# Payload.net
KiCad netlist of a schematic drawn in EAGLE
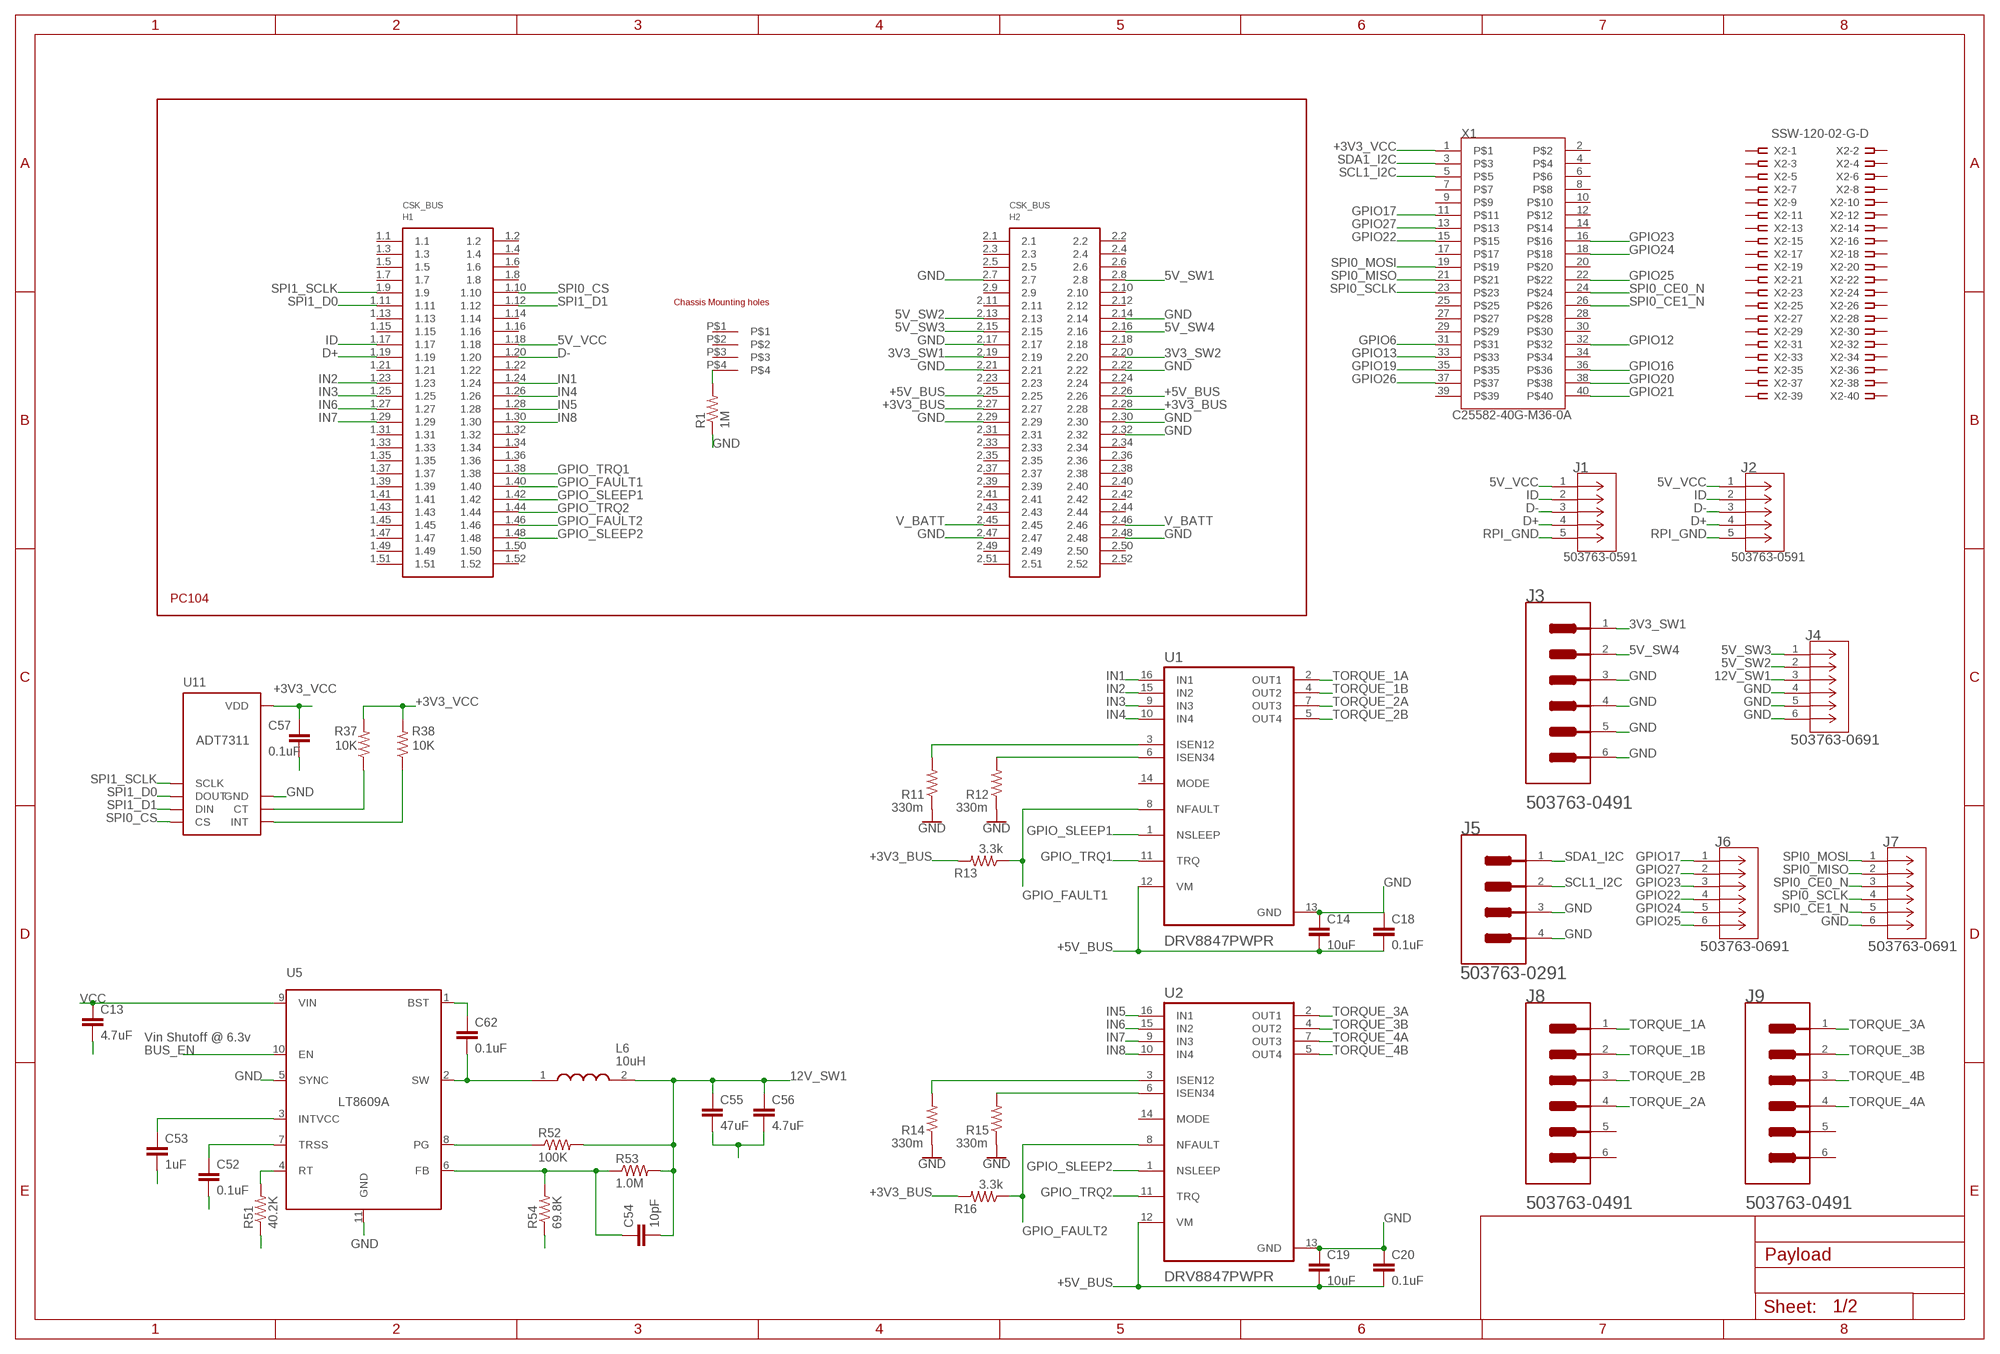
[diagram p0: schematic, sheet 1]
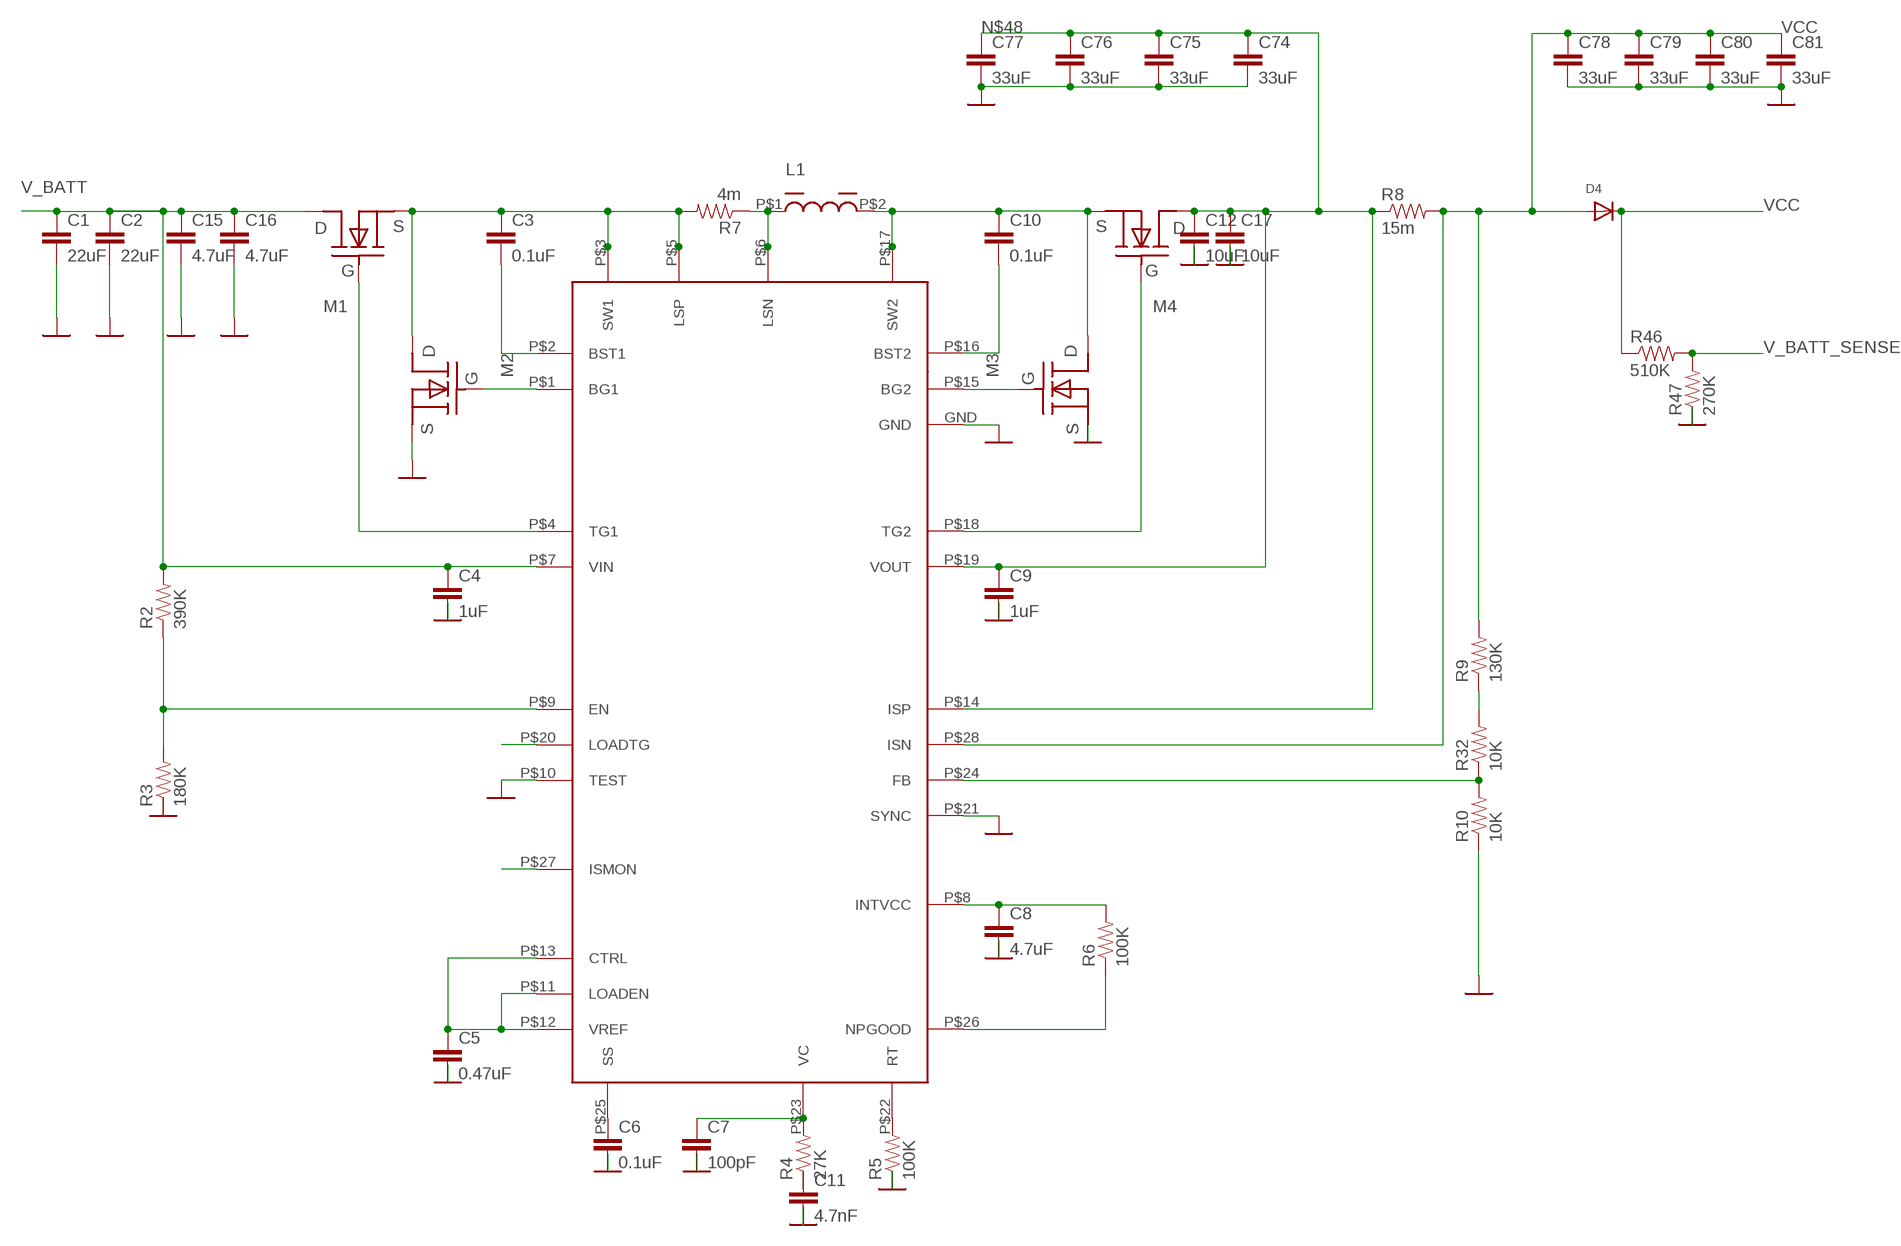
[diagram p1: schematic, sheet 2]

(export (version "E")
  (design (tool "Eeschema 10.0.6"))
  (components
    (comp (ref "C13")
      (value "4.7uF")
      (footprint "eagle-import:0805")
      (libsource (lib "eagle-import") (part "CAP0805"))
    )
    (comp (ref "C14")
      (value "10uF")
      (footprint "eagle-import:0805")
      (libsource (lib "eagle-import") (part "CAP0805"))
    )
    (comp (ref "C18")
      (value "0.1uF")
      (footprint "eagle-import:0805")
      (libsource (lib "eagle-import") (part "CAP0805"))
    )
    (comp (ref "C19")
      (value "10uF")
      (footprint "eagle-import:0805")
      (libsource (lib "eagle-import") (part "CAP0805"))
    )
    (comp (ref "C20")
      (value "0.1uF")
      (footprint "eagle-import:0805")
      (libsource (lib "eagle-import") (part "CAP0805"))
    )
    (comp (ref "C52")
      (value "0.1uF")
      (footprint "eagle-import:0805")
      (libsource (lib "eagle-import") (part "CAP0805"))
    )
    (comp (ref "C53")
      (value "1uF")
      (footprint "eagle-import:0805")
      (libsource (lib "eagle-import") (part "CAP0805"))
    )
    (comp (ref "C54")
      (value "10pF")
      (footprint "eagle-import:0805")
      (libsource (lib "eagle-import") (part "CAP0805"))
    )
    (comp (ref "C55")
      (value "47uF")
      (footprint "eagle-import:1210")
      (libsource (lib "eagle-import") (part "CAP1210"))
    )
    (comp (ref "C56")
      (value "4.7uF")
      (footprint "eagle-import:0805")
      (libsource (lib "eagle-import") (part "CAP0805"))
    )
    (comp (ref "C57")
      (value "0.1uF")
      (footprint "eagle-import:0805")
      (libsource (lib "eagle-import") (part "CAP0805"))
    )
    (comp (ref "C62")
      (value "0.1uF")
      (footprint "eagle-import:0805")
      (libsource (lib "eagle-import") (part "CAP0805"))
    )
    (comp (ref "H1")
      (value "PC104_WCONN")
      (footprint "eagle-import:PC104_WCONN")
      (libsource (lib "eagle-import") (part "PC104_WCONN"))
    )
    (comp (ref "J1")
      (value "503763-0591")
      (footprint "eagle-import:CONN_5037630591_MOL")
      (fields (field (name "COPYRIGHT") "Copyright (C) 2018 Accelerated Designs. All rights reserved"))
      (libsource (lib "eagle-import") (part "503763-0591"))
    )
    (comp (ref "J2")
      (value "503763-0591")
      (footprint "eagle-import:CONN_5037630591_MOL")
      (fields (field (name "COPYRIGHT") "Copyright (C) 2018 Accelerated Designs. All rights reserved"))
      (libsource (lib "eagle-import") (part "503763-0591"))
    )
    (comp (ref "J3")
      (value "MOLEX_503763-0491MOLEX_503763-0491_0_0")
      (footprint "eagle-import:MOLEX_503763-0491_0")
      (fields
        (field (name "DIGIKEY_PART_NUMBER") "WM10655CT-ND")
        (field (name "MF") "Molex")
        (field (name "MOUSER_PART_NUMBER") "538-503763-0491")
      )
      (libsource (lib "eagle-import") (part "MOLEX_503763-0491MOLEX_503763-0491_0_0"))
    )
    (comp (ref "J4")
      (value "503763-0691")
      (footprint "eagle-import:CONN_503763-0691_MOL")
      (fields (field (name "COPYRIGHT") "Copyright (C) 2018 Accelerated Designs. All rights reserved"))
      (libsource (lib "eagle-import") (part "503763-0691"))
    )
    (comp (ref "J5")
      (value "MOLEX_503763-0291MOLEX_503763-0291_0_0")
      (footprint "eagle-import:MOLEX_503763-0291_0")
      (fields
        (field (name "DIGIKEY_PART_NUMBER") "WM10654CT-ND")
        (field (name "MF") "Molex")
        (field (name "MOUSER_PART_NUMBER") "538-503763-0291")
      )
      (libsource (lib "eagle-import") (part "MOLEX_503763-0291MOLEX_503763-0291_0_0"))
    )
    (comp (ref "J6")
      (value "503763-0691")
      (footprint "eagle-import:CONN_503763-0691_MOL")
      (fields (field (name "COPYRIGHT") "Copyright (C) 2018 Accelerated Designs. All rights reserved"))
      (libsource (lib "eagle-import") (part "503763-0691"))
    )
    (comp (ref "J7")
      (value "503763-0691")
      (footprint "eagle-import:CONN_503763-0691_MOL")
      (fields (field (name "COPYRIGHT") "Copyright (C) 2018 Accelerated Designs. All rights reserved"))
      (libsource (lib "eagle-import") (part "503763-0691"))
    )
    (comp (ref "J8")
      (value "MOLEX_503763-0491MOLEX_503763-0491_0_0")
      (footprint "eagle-import:MOLEX_503763-0491_0")
      (fields
        (field (name "DIGIKEY_PART_NUMBER") "WM10655CT-ND")
        (field (name "MF") "Molex")
        (field (name "MOUSER_PART_NUMBER") "538-503763-0491")
      )
      (libsource (lib "eagle-import") (part "MOLEX_503763-0491MOLEX_503763-0491_0_0"))
    )
    (comp (ref "J9")
      (value "MOLEX_503763-0491MOLEX_503763-0491_0_0")
      (footprint "eagle-import:MOLEX_503763-0491_0")
      (fields
        (field (name "DIGIKEY_PART_NUMBER") "WM10655CT-ND")
        (field (name "MF") "Molex")
        (field (name "MOUSER_PART_NUMBER") "538-503763-0491")
      )
      (libsource (lib "eagle-import") (part "MOLEX_503763-0491MOLEX_503763-0491_0_0"))
    )
    (comp (ref "L6")
      (value "10uH")
      (footprint "eagle-import:XFL4030472MEB")
      (fields
        (field (name "ARROW_PART_NUMBER") "XFL4020-222MEC")
        (field (name "MOUSER_PART_NUMBER") "994-XFL4020-222MEC")
      )
      (libsource (lib "eagle-import") (part "XFL4020-222MEC"))
    )
    (comp (ref "R1")
      (value "1M")
      (footprint "eagle-import:0805")
      (libsource (lib "eagle-import") (part "RESISTOR0805-RES"))
    )
    (comp (ref "R11")
      (value "330m")
      (footprint "eagle-import:0805")
      (libsource (lib "eagle-import") (part "RESISTOR0805-RES"))
    )
    (comp (ref "R12")
      (value "330m")
      (footprint "eagle-import:0805")
      (libsource (lib "eagle-import") (part "RESISTOR0805-RES"))
    )
    (comp (ref "R13")
      (value "3.3k")
      (footprint "eagle-import:0805")
      (libsource (lib "eagle-import") (part "RESISTOR0805-RES"))
    )
    (comp (ref "R14")
      (value "330m")
      (footprint "eagle-import:0805")
      (libsource (lib "eagle-import") (part "RESISTOR0805-RES"))
    )
    (comp (ref "R15")
      (value "330m")
      (footprint "eagle-import:0805")
      (libsource (lib "eagle-import") (part "RESISTOR0805-RES"))
    )
    (comp (ref "R16")
      (value "3.3k")
      (footprint "eagle-import:0805")
      (libsource (lib "eagle-import") (part "RESISTOR0805-RES"))
    )
    (comp (ref "R37")
      (value "10K")
      (footprint "eagle-import:0805")
      (libsource (lib "eagle-import") (part "RESISTOR0805-RES"))
    )
    (comp (ref "R38")
      (value "10K")
      (footprint "eagle-import:0805")
      (libsource (lib "eagle-import") (part "RESISTOR0805-RES"))
    )
    (comp (ref "R51")
      (value "40.2K")
      (footprint "eagle-import:0805")
      (libsource (lib "eagle-import") (part "RESISTOR0805-RES"))
    )
    (comp (ref "R52")
      (value "100K")
      (footprint "eagle-import:0805")
      (libsource (lib "eagle-import") (part "RESISTOR0805-RES"))
    )
    (comp (ref "R53")
      (value "1.0M")
      (footprint "eagle-import:0805")
      (libsource (lib "eagle-import") (part "RESISTOR0805-RES"))
    )
    (comp (ref "R54")
      (value "69.8K")
      (footprint "eagle-import:0805")
      (libsource (lib "eagle-import") (part "RESISTOR0805-RES"))
    )
    (comp (ref "U1")
      (value "DRV8847PWPR")
      (footprint "eagle-import:SOP65P640X120-17N")
      (fields (field (name "MF") "Texas Instruments"))
      (libsource (lib "eagle-import") (part "DRV8847PWPR"))
    )
    (comp (ref "U2")
      (value "DRV8847PWPR")
      (footprint "eagle-import:SOP65P640X120-17N")
      (fields (field (name "MF") "Texas Instruments"))
      (libsource (lib "eagle-import") (part "DRV8847PWPR"))
    )
    (comp (ref "U5")
      (value "LT8609A")
      (footprint "eagle-import:MSOP-10_MSE")
      (libsource (lib "eagle-import") (part "LT8609A"))
    )
    (comp (ref "U11")
      (value "ADT7311")
      (footprint "eagle-import:SOIC-8")
      (libsource (lib "eagle-import") (part "ADT7311"))
    )
    (comp (ref "X1")
      (value "C25582-40G-M36-0A")
      (footprint "eagle-import:ADAFRUIT_C25582-40G-M36-0A_0")
      (libsource (lib "eagle-import") (part "C25582-40G-M36-0A"))
    )
    (comp (ref "X2")
      (value "SSW-120-02-G-D")
      (footprint "eagle-import:SSW-120-02-G-D")
      (fields (field (name "MF") "Samtec Inc."))
      (libsource (lib "eagle-import") (part "SSW-120-02-G-D"))
    )
    (comp (ref "C1")
      (value "22uF")
      (footprint "eagle-import:0805")
      (libsource (lib "eagle-import") (part "CAP0805"))
    )
    (comp (ref "C2")
      (value "22uF")
      (footprint "eagle-import:0805")
      (libsource (lib "eagle-import") (part "CAP0805"))
    )
    (comp (ref "C3")
      (value "0.1uF")
      (footprint "eagle-import:0805")
      (libsource (lib "eagle-import") (part "CAP0805"))
    )
    (comp (ref "C4")
      (value "1uF")
      (footprint "eagle-import:0805")
      (libsource (lib "eagle-import") (part "CAP0805"))
    )
    (comp (ref "C5")
      (value "0.47uF")
      (footprint "eagle-import:0805")
      (libsource (lib "eagle-import") (part "CAP0805"))
    )
    (comp (ref "C6")
      (value "0.1uF")
      (footprint "eagle-import:0805")
      (libsource (lib "eagle-import") (part "CAP0805"))
    )
    (comp (ref "C7")
      (value "100pF")
      (footprint "eagle-import:0805")
      (libsource (lib "eagle-import") (part "CAP0805"))
    )
    (comp (ref "C8")
      (value "4.7uF")
      (footprint "eagle-import:0805")
      (libsource (lib "eagle-import") (part "CAP0805"))
    )
    (comp (ref "C9")
      (value "1uF")
      (footprint "eagle-import:0805")
      (libsource (lib "eagle-import") (part "CAP0805"))
    )
    (comp (ref "C10")
      (value "0.1uF")
      (footprint "eagle-import:0805")
      (libsource (lib "eagle-import") (part "CAP0805"))
    )
    (comp (ref "C11")
      (value "4.7nF")
      (footprint "eagle-import:0805")
      (libsource (lib "eagle-import") (part "CAP0805"))
    )
    (comp (ref "C12")
      (value "10uF")
      (footprint "eagle-import:0805")
      (libsource (lib "eagle-import") (part "CAP0805"))
    )
    (comp (ref "C15")
      (value "4.7uF")
      (footprint "eagle-import:0805")
      (libsource (lib "eagle-import") (part "CAP0805"))
    )
    (comp (ref "C16")
      (value "4.7uF")
      (footprint "eagle-import:0805")
      (libsource (lib "eagle-import") (part "CAP0805"))
    )
    (comp (ref "C17")
      (value "10uF")
      (footprint "eagle-import:0805")
      (libsource (lib "eagle-import") (part "CAP0805"))
    )
    (comp (ref "C74")
      (value "33uF")
      (footprint "eagle-import:1206")
      (libsource (lib "eagle-import") (part "CAP1206"))
    )
    (comp (ref "C75")
      (value "33uF")
      (footprint "eagle-import:1206")
      (libsource (lib "eagle-import") (part "CAP1206"))
    )
    (comp (ref "C76")
      (value "33uF")
      (footprint "eagle-import:1206")
      (libsource (lib "eagle-import") (part "CAP1206"))
    )
    (comp (ref "C77")
      (value "33uF")
      (footprint "eagle-import:1206")
      (libsource (lib "eagle-import") (part "CAP1206"))
    )
    (comp (ref "C78")
      (value "33uF")
      (footprint "eagle-import:1206")
      (libsource (lib "eagle-import") (part "CAP1206"))
    )
    (comp (ref "C79")
      (value "33uF")
      (footprint "eagle-import:1206")
      (libsource (lib "eagle-import") (part "CAP1206"))
    )
    (comp (ref "C80")
      (value "33uF")
      (footprint "eagle-import:1206")
      (libsource (lib "eagle-import") (part "CAP1206"))
    )
    (comp (ref "C81")
      (value "33uF")
      (footprint "eagle-import:1206")
      (libsource (lib "eagle-import") (part "CAP1206"))
    )
    (comp (ref "D4")
      (value "DIODE_SOD-123FL")
      (footprint "eagle-import:SOD-123FL")
      (libsource (lib "eagle-import") (part "DIODE_SOD-123FL"))
    )
    (comp (ref "L1")
      (value "6uH")
      (footprint "eagle-import:7443551600")
      (libsource (lib "eagle-import") (part "7443551600"))
    )
    (comp (ref "M1")
      (value "BSZ100N06LS3")
      (footprint "eagle-import:BSZ100N06LS3")
      (libsource (lib "eagle-import") (part "BSZ100N06LS3"))
    )
    (comp (ref "M2")
      (value "BSZ100N06LS3")
      (footprint "eagle-import:BSZ100N06LS3")
      (libsource (lib "eagle-import") (part "BSZ100N06LS3"))
    )
    (comp (ref "M3")
      (value "BSZ033NE2LS5")
      (footprint "eagle-import:BSZ100N06LS3")
      (libsource (lib "eagle-import") (part "BSZ100N06LS3"))
    )
    (comp (ref "M4")
      (value "BSZ033NE2LS5")
      (footprint "eagle-import:BSZ100N06LS3")
      (libsource (lib "eagle-import") (part "BSZ100N06LS3"))
    )
    (comp (ref "R2")
      (value "390K")
      (footprint "eagle-import:0805")
      (libsource (lib "eagle-import") (part "RESISTOR0805-RES"))
    )
    (comp (ref "R3")
      (value "180K")
      (footprint "eagle-import:0805")
      (libsource (lib "eagle-import") (part "RESISTOR0805-RES"))
    )
    (comp (ref "R4")
      (value "27K")
      (footprint "eagle-import:0805")
      (libsource (lib "eagle-import") (part "RESISTOR0805-RES"))
    )
    (comp (ref "R5")
      (value "100K")
      (footprint "eagle-import:0805")
      (libsource (lib "eagle-import") (part "RESISTOR0805-RES"))
    )
    (comp (ref "R6")
      (value "100K")
      (footprint "eagle-import:0805")
      (libsource (lib "eagle-import") (part "RESISTOR0805-RES"))
    )
    (comp (ref "R7")
      (value "4m")
      (footprint "eagle-import:0805")
      (libsource (lib "eagle-import") (part "RESISTOR0805-RES"))
    )
    (comp (ref "R8")
      (value "15m")
      (footprint "eagle-import:0805")
      (libsource (lib "eagle-import") (part "RESISTOR0805-RES"))
    )
    (comp (ref "R9")
      (value "130K")
      (footprint "eagle-import:0805")
      (libsource (lib "eagle-import") (part "RESISTOR0805-RES"))
    )
    (comp (ref "R10")
      (value "10K")
      (footprint "eagle-import:0805")
      (libsource (lib "eagle-import") (part "RESISTOR0805-RES"))
    )
    (comp (ref "R32")
      (value "10K")
      (footprint "eagle-import:0805")
      (libsource (lib "eagle-import") (part "RESISTOR0805-RES"))
    )
    (comp (ref "R46")
      (value "510K")
      (footprint "eagle-import:0805")
      (libsource (lib "eagle-import") (part "RESISTOR0805-RES"))
    )
    (comp (ref "R47")
      (value "270K")
      (footprint "eagle-import:0805")
      (libsource (lib "eagle-import") (part "RESISTOR0805-RES"))
    )
    (comp (ref "U$2")
      (value "LT8309EFE")
      (footprint "eagle-import:LT8309EFE")
      (libsource (lib "eagle-import") (part "LT8309EFE"))
    )
  )
  (nets
    (net (code "1") (name "+3V3_BUS") (class "Default")
      (node (ref "H1") (pin "2.27") (pinfunction "2.27_2.27") (pintype "bidirectional"))
      (node (ref "H1") (pin "2.28") (pinfunction "2.28_2.28") (pintype "bidirectional"))
      (node (ref "R13") (pin "2") (pinfunction "2_2") (pintype "passive"))
      (node (ref "R16") (pin "2") (pinfunction "2_2") (pintype "passive"))
    )
    (net (code "2") (name "+3V3_VCC") (class "Default")
      (node (ref "C57") (pin "1") (pinfunction "1_1") (pintype "passive"))
      (node (ref "R37") (pin "2") (pinfunction "2_2") (pintype "passive"))
      (node (ref "R38") (pin "2") (pinfunction "2_2") (pintype "passive"))
      (node (ref "U11") (pin "8") (pinfunction "VDD_8") (pintype "bidirectional"))
      (node (ref "X1") (pin "1") (pinfunction "P$1_1") (pintype "bidirectional"))
    )
    (net (code "3") (name "+5V_BUS") (class "Default")
      (node (ref "C14") (pin "2") (pinfunction "2_2") (pintype "passive"))
      (node (ref "C18") (pin "2") (pinfunction "2_2") (pintype "passive"))
      (node (ref "C19") (pin "2") (pinfunction "2_2") (pintype "passive"))
      (node (ref "C20") (pin "2") (pinfunction "2_2") (pintype "passive"))
      (node (ref "H1") (pin "2.25") (pinfunction "2.25_2.25") (pintype "bidirectional"))
      (node (ref "H1") (pin "2.26") (pinfunction "2.26_2.26") (pintype "bidirectional"))
      (node (ref "U1") (pin "12") (pinfunction "VM_12") (pintype "bidirectional"))
      (node (ref "U2") (pin "12") (pinfunction "VM_12") (pintype "bidirectional"))
    )
    (net (code "4") (name "3V3_SW1") (class "Default")
      (node (ref "H1") (pin "2.19") (pinfunction "2.19_2.19") (pintype "bidirectional"))
      (node (ref "J3") (pin "1") (pinfunction "1_1") (pintype "passive"))
    )
    (net (code "5") (name "3V3_SW2") (class "Default")
      (node (ref "H1") (pin "2.20") (pinfunction "2.20_2.20") (pintype "bidirectional"))
    )
    (net (code "6") (name "5V_SW1") (class "Default")
      (node (ref "H1") (pin "2.8") (pinfunction "2.8_2.8") (pintype "bidirectional"))
    )
    (net (code "7") (name "5V_SW2") (class "Default")
      (node (ref "H1") (pin "2.13") (pinfunction "2.13_2.13") (pintype "bidirectional"))
      (node (ref "J4") (pin "2") (pinfunction "2_2") (pintype "passive"))
    )
    (net (code "8") (name "5V_SW3") (class "Default")
      (node (ref "H1") (pin "2.15") (pinfunction "2.15_2.15") (pintype "bidirectional"))
      (node (ref "J4") (pin "1") (pinfunction "1_1") (pintype "passive"))
    )
    (net (code "9") (name "5V_SW4") (class "Default")
      (node (ref "H1") (pin "2.16") (pinfunction "2.16_2.16") (pintype "bidirectional"))
      (node (ref "J3") (pin "2") (pinfunction "2_2") (pintype "passive"))
    )
    (net (code "10") (name "5V_VCC") (class "Default")
      (node (ref "H1") (pin "1.18") (pinfunction "1.18_1.18") (pintype "bidirectional"))
      (node (ref "J1") (pin "1") (pinfunction "1_1") (pintype "passive"))
      (node (ref "J2") (pin "1") (pinfunction "1_1") (pintype "passive"))
    )
    (net (code "11") (name "12V_SW1") (class "Default")
      (node (ref "C54") (pin "2") (pinfunction "2_2") (pintype "passive"))
      (node (ref "C55") (pin "1") (pinfunction "1_1") (pintype "passive"))
      (node (ref "C56") (pin "1") (pinfunction "1_1") (pintype "passive"))
      (node (ref "J4") (pin "3") (pinfunction "3_3") (pintype "passive"))
      (node (ref "L6") (pin "2") (pinfunction "2_2") (pintype "bidirectional"))
      (node (ref "R52") (pin "2") (pinfunction "2_2") (pintype "passive"))
      (node (ref "R53") (pin "2") (pinfunction "2_2") (pintype "passive"))
    )
    (net (code "12") (name "BUS_EN") (class "Default")
      (node (ref "U5") (pin "10") (pinfunction "EN_10") (pintype "bidirectional"))
    )
    (net (code "13") (name "D+") (class "Default")
      (node (ref "H1") (pin "1.19") (pinfunction "1.19_1.19") (pintype "bidirectional"))
      (node (ref "J1") (pin "4") (pinfunction "4_4") (pintype "passive"))
      (node (ref "J2") (pin "4") (pinfunction "4_4") (pintype "passive"))
    )
    (net (code "14") (name "D-") (class "Default")
      (node (ref "H1") (pin "1.20") (pinfunction "1.20_1.20") (pintype "bidirectional"))
      (node (ref "J1") (pin "3") (pinfunction "3_3") (pintype "passive"))
      (node (ref "J2") (pin "3") (pinfunction "3_3") (pintype "passive"))
    )
    (net (code "15") (name "GND") (class "Default")
      (node (ref "C1") (pin "2") (pinfunction "2_2") (pintype "passive"))
      (node (ref "C11") (pin "2") (pinfunction "2_2") (pintype "passive"))
      (node (ref "C12") (pin "2") (pinfunction "2_2") (pintype "passive"))
      (node (ref "C14") (pin "1") (pinfunction "1_1") (pintype "passive"))
      (node (ref "C15") (pin "2") (pinfunction "2_2") (pintype "passive"))
      (node (ref "C16") (pin "2") (pinfunction "2_2") (pintype "passive"))
      (node (ref "C17") (pin "2") (pinfunction "2_2") (pintype "passive"))
      (node (ref "C18") (pin "1") (pinfunction "1_1") (pintype "passive"))
      (node (ref "C19") (pin "1") (pinfunction "1_1") (pintype "passive"))
      (node (ref "C2") (pin "2") (pinfunction "2_2") (pintype "passive"))
      (node (ref "C20") (pin "1") (pinfunction "1_1") (pintype "passive"))
      (node (ref "C4") (pin "2") (pinfunction "2_2") (pintype "passive"))
      (node (ref "C5") (pin "2") (pinfunction "2_2") (pintype "passive"))
      (node (ref "C52") (pin "2") (pinfunction "2_2") (pintype "passive"))
      (node (ref "C53") (pin "2") (pinfunction "2_2") (pintype "passive"))
      (node (ref "C55") (pin "2") (pinfunction "2_2") (pintype "passive"))
      (node (ref "C56") (pin "2") (pinfunction "2_2") (pintype "passive"))
      (node (ref "C57") (pin "2") (pinfunction "2_2") (pintype "passive"))
      (node (ref "C6") (pin "2") (pinfunction "2_2") (pintype "passive"))
      (node (ref "C7") (pin "2") (pinfunction "2_2") (pintype "passive"))
      (node (ref "C74") (pin "2") (pinfunction "2_2") (pintype "passive"))
      (node (ref "C75") (pin "2") (pinfunction "2_2") (pintype "passive"))
      (node (ref "C76") (pin "2") (pinfunction "2_2") (pintype "passive"))
      (node (ref "C77") (pin "2") (pinfunction "2_2") (pintype "passive"))
      (node (ref "C78") (pin "2") (pinfunction "2_2") (pintype "passive"))
      (node (ref "C79") (pin "2") (pinfunction "2_2") (pintype "passive"))
      (node (ref "C8") (pin "2") (pinfunction "2_2") (pintype "passive"))
      (node (ref "C80") (pin "2") (pinfunction "2_2") (pintype "passive"))
      (node (ref "C81") (pin "2") (pinfunction "2_2") (pintype "passive"))
      (node (ref "C9") (pin "2") (pinfunction "2_2") (pintype "passive"))
      (node (ref "H1") (pin "2.14") (pinfunction "2.14_2.14") (pintype "bidirectional"))
      (node (ref "H1") (pin "2.17") (pinfunction "2.17_2.17") (pintype "bidirectional"))
      (node (ref "H1") (pin "2.21") (pinfunction "2.21_2.21") (pintype "bidirectional"))
      (node (ref "H1") (pin "2.22") (pinfunction "2.22_2.22") (pintype "bidirectional"))
      (node (ref "H1") (pin "2.29") (pinfunction "2.29_2.29") (pintype "bidirectional"))
      (node (ref "H1") (pin "2.30") (pinfunction "2.30_2.30") (pintype "bidirectional"))
      (node (ref "H1") (pin "2.32") (pinfunction "2.32_2.32") (pintype "bidirectional"))
      (node (ref "H1") (pin "2.47") (pinfunction "2.47_2.47") (pintype "bidirectional"))
      (node (ref "H1") (pin "2.48") (pinfunction "2.48_2.48") (pintype "bidirectional"))
      (node (ref "H1") (pin "2.7") (pinfunction "2.7_2.7") (pintype "bidirectional"))
      (node (ref "J3") (pin "3") (pinfunction "3_3") (pintype "passive"))
      (node (ref "J3") (pin "4") (pinfunction "4_4") (pintype "passive"))
      (node (ref "J3") (pin "5") (pinfunction "MNT_1_5") (pintype "passive"))
      (node (ref "J3") (pin "6") (pinfunction "MNT_2_6") (pintype "passive"))
      (node (ref "J4") (pin "4") (pinfunction "4_4") (pintype "passive"))
      (node (ref "J4") (pin "5") (pinfunction "5_5") (pintype "passive"))
      (node (ref "J4") (pin "6") (pinfunction "6_6") (pintype "passive"))
      (node (ref "J5") (pin "3") (pinfunction "MNT_1_3") (pintype "bidirectional"))
      (node (ref "J5") (pin "4") (pinfunction "MNT_2_4") (pintype "bidirectional"))
      (node (ref "J7") (pin "6") (pinfunction "6_6") (pintype "passive"))
      (node (ref "M2") (pin "P$2") (pinfunction "S_P$2") (pintype "input"))
      (node (ref "M2") (pin "P$3") (pinfunction "S_P$3") (pintype "input"))
      (node (ref "M2") (pin "P$4") (pinfunction "S_P$4") (pintype "input"))
      (node (ref "M3") (pin "P$2") (pinfunction "S_P$2") (pintype "input"))
      (node (ref "M3") (pin "P$3") (pinfunction "S_P$3") (pintype "input"))
      (node (ref "M3") (pin "P$4") (pinfunction "S_P$4") (pintype "input"))
      (node (ref "R1") (pin "1") (pinfunction "1_1") (pintype "passive"))
      (node (ref "R10") (pin "1") (pinfunction "1_1") (pintype "passive"))
      (node (ref "R11") (pin "1") (pinfunction "1_1") (pintype "passive"))
      (node (ref "R12") (pin "1") (pinfunction "1_1") (pintype "passive"))
      (node (ref "R14") (pin "1") (pinfunction "1_1") (pintype "passive"))
      (node (ref "R15") (pin "1") (pinfunction "1_1") (pintype "passive"))
      (node (ref "R3") (pin "1") (pinfunction "1_1") (pintype "passive"))
      (node (ref "R47") (pin "1") (pinfunction "1_1") (pintype "passive"))
      (node (ref "R5") (pin "1") (pinfunction "1_1") (pintype "passive"))
      (node (ref "R51") (pin "1") (pinfunction "1_1") (pintype "passive"))
      (node (ref "R54") (pin "1") (pinfunction "1_1") (pintype "passive"))
      (node (ref "U$2") (pin "GND") (pinfunction "GND_GND") (pintype "bidirectional"))
      (node (ref "U$2") (pin "P$10") (pinfunction "TEST_P$10") (pintype "bidirectional"))
      (node (ref "U$2") (pin "P$21") (pinfunction "SYNC_P$21") (pintype "bidirectional"))
      (node (ref "U1") (pin "13") (pinfunction "GND_13") (pintype "power_in"))
      (node (ref "U11") (pin "7") (pinfunction "GND_7") (pintype "bidirectional"))
      (node (ref "U2") (pin "13") (pinfunction "GND_13") (pintype "power_in"))
      (node (ref "U5") (pin "11") (pinfunction "GND_11") (pintype "bidirectional"))
      (node (ref "U5") (pin "5") (pinfunction "SYNC_5") (pintype "bidirectional"))
    )
    (net (code "16") (name "GPIO6") (class "Default")
      (node (ref "X1") (pin "31") (pinfunction "P$31_31") (pintype "bidirectional"))
    )
    (net (code "17") (name "GPIO12") (class "Default")
      (node (ref "X1") (pin "32") (pinfunction "P$32_32") (pintype "bidirectional"))
    )
    (net (code "18") (name "GPIO13") (class "Default")
      (node (ref "X1") (pin "33") (pinfunction "P$33_33") (pintype "bidirectional"))
    )
    (net (code "19") (name "GPIO16") (class "Default")
      (node (ref "X1") (pin "36") (pinfunction "P$36_36") (pintype "bidirectional"))
    )
    (net (code "20") (name "GPIO17") (class "Default")
      (node (ref "J6") (pin "1") (pinfunction "1_1") (pintype "passive"))
      (node (ref "X1") (pin "11") (pinfunction "P$11_11") (pintype "bidirectional"))
    )
    (net (code "21") (name "GPIO19") (class "Default")
      (node (ref "X1") (pin "35") (pinfunction "P$35_35") (pintype "bidirectional"))
    )
    (net (code "22") (name "GPIO20") (class "Default")
      (node (ref "X1") (pin "38") (pinfunction "P$38_38") (pintype "bidirectional"))
    )
    (net (code "23") (name "GPIO21") (class "Default")
      (node (ref "X1") (pin "40") (pinfunction "P$40_40") (pintype "bidirectional"))
    )
    (net (code "24") (name "GPIO22") (class "Default")
      (node (ref "J6") (pin "4") (pinfunction "4_4") (pintype "passive"))
      (node (ref "X1") (pin "15") (pinfunction "P$15_15") (pintype "bidirectional"))
    )
    (net (code "25") (name "GPIO23") (class "Default")
      (node (ref "J6") (pin "3") (pinfunction "3_3") (pintype "passive"))
      (node (ref "X1") (pin "16") (pinfunction "P$16_16") (pintype "bidirectional"))
    )
    (net (code "26") (name "GPIO24") (class "Default")
      (node (ref "J6") (pin "5") (pinfunction "5_5") (pintype "passive"))
      (node (ref "X1") (pin "18") (pinfunction "P$18_18") (pintype "bidirectional"))
    )
    (net (code "27") (name "GPIO25") (class "Default")
      (node (ref "J6") (pin "6") (pinfunction "6_6") (pintype "passive"))
      (node (ref "X1") (pin "22") (pinfunction "P$22_22") (pintype "bidirectional"))
    )
    (net (code "28") (name "GPIO26") (class "Default")
      (node (ref "X1") (pin "37") (pinfunction "P$37_37") (pintype "bidirectional"))
    )
    (net (code "29") (name "GPIO27") (class "Default")
      (node (ref "J6") (pin "2") (pinfunction "2_2") (pintype "passive"))
      (node (ref "X1") (pin "13") (pinfunction "P$13_13") (pintype "bidirectional"))
    )
    (net (code "30") (name "GPIO_FAULT1") (class "Default")
      (node (ref "H1") (pin "1.40") (pinfunction "1.40_1.40") (pintype "bidirectional"))
      (node (ref "R13") (pin "1") (pinfunction "1_1") (pintype "passive"))
      (node (ref "U1") (pin "8") (pinfunction "NFAULT_8") (pintype "bidirectional"))
    )
    (net (code "31") (name "GPIO_FAULT2") (class "Default")
      (node (ref "H1") (pin "1.46") (pinfunction "1.46_1.46") (pintype "bidirectional"))
      (node (ref "R16") (pin "1") (pinfunction "1_1") (pintype "passive"))
      (node (ref "U2") (pin "8") (pinfunction "NFAULT_8") (pintype "bidirectional"))
    )
    (net (code "32") (name "GPIO_SLEEP1") (class "Default")
      (node (ref "H1") (pin "1.42") (pinfunction "1.42_1.42") (pintype "bidirectional"))
      (node (ref "U1") (pin "1") (pinfunction "NSLEEP_1") (pintype "bidirectional"))
    )
    (net (code "33") (name "GPIO_SLEEP2") (class "Default")
      (node (ref "H1") (pin "1.48") (pinfunction "1.48_1.48") (pintype "bidirectional"))
      (node (ref "U2") (pin "1") (pinfunction "NSLEEP_1") (pintype "bidirectional"))
    )
    (net (code "34") (name "GPIO_TRQ1") (class "Default")
      (node (ref "H1") (pin "1.38") (pinfunction "1.38_1.38") (pintype "bidirectional"))
      (node (ref "U1") (pin "11") (pinfunction "TRQ_11") (pintype "bidirectional"))
    )
    (net (code "35") (name "GPIO_TRQ2") (class "Default")
      (node (ref "H1") (pin "1.44") (pinfunction "1.44_1.44") (pintype "bidirectional"))
      (node (ref "U2") (pin "11") (pinfunction "TRQ_11") (pintype "bidirectional"))
    )
    (net (code "36") (name "ID") (class "Default")
      (node (ref "H1") (pin "1.17") (pinfunction "1.17_1.17") (pintype "bidirectional"))
      (node (ref "J1") (pin "2") (pinfunction "2_2") (pintype "passive"))
      (node (ref "J2") (pin "2") (pinfunction "2_2") (pintype "passive"))
    )
    (net (code "37") (name "IN1") (class "Default")
      (node (ref "H1") (pin "1.24") (pinfunction "1.24_1.24") (pintype "bidirectional"))
      (node (ref "U1") (pin "16") (pinfunction "IN1_16") (pintype "input"))
    )
    (net (code "38") (name "IN2") (class "Default")
      (node (ref "H1") (pin "1.23") (pinfunction "1.23_1.23") (pintype "bidirectional"))
      (node (ref "U1") (pin "15") (pinfunction "IN2_15") (pintype "input"))
    )
    (net (code "39") (name "IN3") (class "Default")
      (node (ref "H1") (pin "1.25") (pinfunction "1.25_1.25") (pintype "bidirectional"))
      (node (ref "U1") (pin "9") (pinfunction "IN3_9") (pintype "input"))
    )
    (net (code "40") (name "IN4") (class "Default")
      (node (ref "H1") (pin "1.26") (pinfunction "1.26_1.26") (pintype "bidirectional"))
      (node (ref "U1") (pin "10") (pinfunction "IN4_10") (pintype "input"))
    )
    (net (code "41") (name "IN5") (class "Default")
      (node (ref "H1") (pin "1.28") (pinfunction "1.28_1.28") (pintype "bidirectional"))
      (node (ref "U2") (pin "16") (pinfunction "IN1_16") (pintype "input"))
    )
    (net (code "42") (name "IN6") (class "Default")
      (node (ref "H1") (pin "1.27") (pinfunction "1.27_1.27") (pintype "bidirectional"))
      (node (ref "U2") (pin "15") (pinfunction "IN2_15") (pintype "input"))
    )
    (net (code "43") (name "IN7") (class "Default")
      (node (ref "H1") (pin "1.29") (pinfunction "1.29_1.29") (pintype "bidirectional"))
      (node (ref "U2") (pin "9") (pinfunction "IN3_9") (pintype "input"))
    )
    (net (code "44") (name "IN8") (class "Default")
      (node (ref "H1") (pin "1.30") (pinfunction "1.30_1.30") (pintype "bidirectional"))
      (node (ref "U2") (pin "10") (pinfunction "IN4_10") (pintype "input"))
    )
    (net (code "45") (name "N$48") (class "Default")
      (node (ref "C12") (pin "1") (pinfunction "1_1") (pintype "passive"))
      (node (ref "C17") (pin "1") (pinfunction "1_1") (pintype "passive"))
      (node (ref "C74") (pin "1") (pinfunction "1_1") (pintype "passive"))
      (node (ref "C75") (pin "1") (pinfunction "1_1") (pintype "passive"))
      (node (ref "C76") (pin "1") (pinfunction "1_1") (pintype "passive"))
      (node (ref "C77") (pin "1") (pinfunction "1_1") (pintype "passive"))
      (node (ref "C9") (pin "1") (pinfunction "1_1") (pintype "passive"))
      (node (ref "M4") (pin "P$5") (pinfunction "D_P$5") (pintype "output"))
      (node (ref "M4") (pin "P$6") (pinfunction "D_P$6") (pintype "output"))
      (node (ref "M4") (pin "P$7") (pinfunction "D_P$7") (pintype "output"))
      (node (ref "M4") (pin "P$8") (pinfunction "D_P$8") (pintype "output"))
      (node (ref "M4") (pin "P$9") (pinfunction "D_P$9") (pintype "output"))
      (node (ref "R8") (pin "1") (pinfunction "1_1") (pintype "passive"))
      (node (ref "U$2") (pin "P$14") (pinfunction "ISP_P$14") (pintype "bidirectional"))
      (node (ref "U$2") (pin "P$19") (pinfunction "VOUT_P$19") (pintype "bidirectional"))
    )
    (net (code "46") (name "Net-(C11-Pad1)") (class "Default")
      (node (ref "C11") (pin "1") (pinfunction "1_1") (pintype "passive"))
      (node (ref "R4") (pin "1") (pinfunction "1_1") (pintype "passive"))
    )
    (net (code "47") (name "Net-(H1-PadP$4)") (class "Default")
      (node (ref "H1") (pin "P$4") (pinfunction "P$4_P$4") (pintype "bidirectional"))
      (node (ref "R1") (pin "2") (pinfunction "2_2") (pintype "passive"))
    )
    (net (code "48") (name "Net-(M1-G)") (class "Default")
      (node (ref "M1") (pin "P$1") (pinfunction "G_P$1") (pintype "input"))
      (node (ref "U$2") (pin "P$4") (pinfunction "TG1_P$4") (pintype "bidirectional"))
    )
    (net (code "49") (name "Net-(M2-G)") (class "Default")
      (node (ref "M2") (pin "P$1") (pinfunction "G_P$1") (pintype "input"))
      (node (ref "U$2") (pin "P$1") (pinfunction "BG1_P$1") (pintype "bidirectional"))
    )
    (net (code "50") (name "Net-(M3-G)") (class "Default")
      (node (ref "M3") (pin "P$1") (pinfunction "G_P$1") (pintype "input"))
      (node (ref "U$2") (pin "P$15") (pinfunction "BG2_P$15") (pintype "bidirectional"))
    )
    (net (code "51") (name "Net-(M4-G)") (class "Default")
      (node (ref "M4") (pin "P$1") (pinfunction "G_P$1") (pintype "input"))
      (node (ref "U$2") (pin "P$18") (pinfunction "TG2_P$18") (pintype "bidirectional"))
    )
    (net (code "52") (name "Net-(R32-Pad2)") (class "Default")
      (node (ref "R32") (pin "2") (pinfunction "2_2") (pintype "passive"))
      (node (ref "R9") (pin "1") (pinfunction "1_1") (pintype "passive"))
    )
    (net (code "53") (name "Net-(U$2-BST1)") (class "Default")
      (node (ref "C3") (pin "2") (pinfunction "2_2") (pintype "passive"))
      (node (ref "U$2") (pin "P$2") (pinfunction "BST1_P$2") (pintype "bidirectional"))
    )
    (net (code "54") (name "Net-(U$2-BST2)") (class "Default")
      (node (ref "C10") (pin "2") (pinfunction "2_2") (pintype "passive"))
      (node (ref "U$2") (pin "P$16") (pinfunction "BST2_P$16") (pintype "bidirectional"))
    )
    (net (code "55") (name "Net-(U$2-CTRL)") (class "Default")
      (node (ref "C5") (pin "1") (pinfunction "1_1") (pintype "passive"))
      (node (ref "U$2") (pin "P$11") (pinfunction "LOADEN_P$11") (pintype "bidirectional"))
      (node (ref "U$2") (pin "P$12") (pinfunction "VREF_P$12") (pintype "bidirectional"))
      (node (ref "U$2") (pin "P$13") (pinfunction "CTRL_P$13") (pintype "bidirectional"))
    )
    (net (code "56") (name "Net-(U$2-EN)") (class "Default")
      (node (ref "R2") (pin "1") (pinfunction "1_1") (pintype "passive"))
      (node (ref "R3") (pin "2") (pinfunction "2_2") (pintype "passive"))
      (node (ref "U$2") (pin "P$9") (pinfunction "EN_P$9") (pintype "bidirectional"))
    )
    (net (code "57") (name "Net-(U$2-FB)") (class "Default")
      (node (ref "R10") (pin "2") (pinfunction "2_2") (pintype "passive"))
      (node (ref "R32") (pin "1") (pinfunction "1_1") (pintype "passive"))
      (node (ref "U$2") (pin "P$24") (pinfunction "FB_P$24") (pintype "bidirectional"))
    )
    (net (code "58") (name "Net-(U$2-INTVCC)") (class "Default")
      (node (ref "C8") (pin "1") (pinfunction "1_1") (pintype "passive"))
      (node (ref "R6") (pin "2") (pinfunction "2_2") (pintype "passive"))
      (node (ref "U$2") (pin "P$8") (pinfunction "INTVCC_P$8") (pintype "bidirectional"))
    )
    (net (code "59") (name "Net-(U$2-LSN)") (class "Default")
      (node (ref "L1") (pin "P$1") (pinfunction "P$1_P$1") (pintype "bidirectional"))
      (node (ref "R7") (pin "1") (pinfunction "1_1") (pintype "passive"))
      (node (ref "U$2") (pin "P$6") (pinfunction "LSN_P$6") (pintype "bidirectional"))
    )
    (net (code "60") (name "Net-(U$2-LSP)") (class "Default")
      (node (ref "C3") (pin "1") (pinfunction "1_1") (pintype "passive"))
      (node (ref "M1") (pin "P$2") (pinfunction "S_P$2") (pintype "input"))
      (node (ref "M1") (pin "P$3") (pinfunction "S_P$3") (pintype "input"))
      (node (ref "M1") (pin "P$4") (pinfunction "S_P$4") (pintype "input"))
      (node (ref "M2") (pin "P$5") (pinfunction "D_P$5") (pintype "output"))
      (node (ref "M2") (pin "P$6") (pinfunction "D_P$6") (pintype "output"))
      (node (ref "M2") (pin "P$7") (pinfunction "D_P$7") (pintype "output"))
      (node (ref "M2") (pin "P$8") (pinfunction "D_P$8") (pintype "output"))
      (node (ref "M2") (pin "P$9") (pinfunction "D_P$9") (pintype "output"))
      (node (ref "R7") (pin "2") (pinfunction "2_2") (pintype "passive"))
      (node (ref "U$2") (pin "P$3") (pinfunction "SW1_P$3") (pintype "bidirectional"))
      (node (ref "U$2") (pin "P$5") (pinfunction "LSP_P$5") (pintype "bidirectional"))
    )
    (net (code "61") (name "Net-(U$2-NPGOOD)") (class "Default")
      (node (ref "R6") (pin "1") (pinfunction "1_1") (pintype "passive"))
      (node (ref "U$2") (pin "P$26") (pinfunction "NPGOOD_P$26") (pintype "bidirectional"))
    )
    (net (code "62") (name "Net-(U$2-RT)") (class "Default")
      (node (ref "R5") (pin "2") (pinfunction "2_2") (pintype "passive"))
      (node (ref "U$2") (pin "P$22") (pinfunction "RT_P$22") (pintype "bidirectional"))
    )
    (net (code "63") (name "Net-(U$2-SS)") (class "Default")
      (node (ref "C6") (pin "1") (pinfunction "1_1") (pintype "passive"))
      (node (ref "U$2") (pin "P$25") (pinfunction "SS_P$25") (pintype "bidirectional"))
    )
    (net (code "64") (name "Net-(U$2-SW2)") (class "Default")
      (node (ref "C10") (pin "1") (pinfunction "1_1") (pintype "passive"))
      (node (ref "L1") (pin "P$2") (pinfunction "P$2_P$2") (pintype "bidirectional"))
      (node (ref "M3") (pin "P$5") (pinfunction "D_P$5") (pintype "output"))
      (node (ref "M3") (pin "P$6") (pinfunction "D_P$6") (pintype "output"))
      (node (ref "M3") (pin "P$7") (pinfunction "D_P$7") (pintype "output"))
      (node (ref "M3") (pin "P$8") (pinfunction "D_P$8") (pintype "output"))
      (node (ref "M3") (pin "P$9") (pinfunction "D_P$9") (pintype "output"))
      (node (ref "M4") (pin "P$2") (pinfunction "S_P$2") (pintype "input"))
      (node (ref "M4") (pin "P$3") (pinfunction "S_P$3") (pintype "input"))
      (node (ref "M4") (pin "P$4") (pinfunction "S_P$4") (pintype "input"))
      (node (ref "U$2") (pin "P$17") (pinfunction "SW2_P$17") (pintype "bidirectional"))
    )
    (net (code "65") (name "Net-(U$2-VC)") (class "Default")
      (node (ref "C7") (pin "1") (pinfunction "1_1") (pintype "passive"))
      (node (ref "R4") (pin "2") (pinfunction "2_2") (pintype "passive"))
      (node (ref "U$2") (pin "P$23") (pinfunction "VC_P$23") (pintype "bidirectional"))
    )
    (net (code "66") (name "Net-(U1-ISEN12)") (class "Default")
      (node (ref "R11") (pin "2") (pinfunction "2_2") (pintype "passive"))
      (node (ref "U1") (pin "3") (pinfunction "ISEN12_3") (pintype "bidirectional"))
    )
    (net (code "67") (name "Net-(U1-ISEN34)") (class "Default")
      (node (ref "R12") (pin "2") (pinfunction "2_2") (pintype "passive"))
      (node (ref "U1") (pin "6") (pinfunction "ISEN34_6") (pintype "bidirectional"))
    )
    (net (code "68") (name "Net-(U2-ISEN12)") (class "Default")
      (node (ref "R14") (pin "2") (pinfunction "2_2") (pintype "passive"))
      (node (ref "U2") (pin "3") (pinfunction "ISEN12_3") (pintype "bidirectional"))
    )
    (net (code "69") (name "Net-(U2-ISEN34)") (class "Default")
      (node (ref "R15") (pin "2") (pinfunction "2_2") (pintype "passive"))
      (node (ref "U2") (pin "6") (pinfunction "ISEN34_6") (pintype "bidirectional"))
    )
    (net (code "70") (name "Net-(U5-BST)") (class "Default")
      (node (ref "C62") (pin "1") (pinfunction "1_1") (pintype "passive"))
      (node (ref "U5") (pin "1") (pinfunction "BST_1") (pintype "bidirectional"))
    )
    (net (code "71") (name "Net-(U5-FB)") (class "Default")
      (node (ref "C54") (pin "1") (pinfunction "1_1") (pintype "passive"))
      (node (ref "R53") (pin "1") (pinfunction "1_1") (pintype "passive"))
      (node (ref "R54") (pin "2") (pinfunction "2_2") (pintype "passive"))
      (node (ref "U5") (pin "6") (pinfunction "FB_6") (pintype "bidirectional"))
    )
    (net (code "72") (name "Net-(U5-INTVCC)") (class "Default")
      (node (ref "C53") (pin "1") (pinfunction "1_1") (pintype "passive"))
      (node (ref "U5") (pin "3") (pinfunction "INTVCC_3") (pintype "bidirectional"))
    )
    (net (code "73") (name "Net-(U5-PG)") (class "Default")
      (node (ref "R52") (pin "1") (pinfunction "1_1") (pintype "passive"))
      (node (ref "U5") (pin "8") (pinfunction "PG_8") (pintype "bidirectional"))
    )
    (net (code "74") (name "Net-(U5-RT)") (class "Default")
      (node (ref "R51") (pin "2") (pinfunction "2_2") (pintype "passive"))
      (node (ref "U5") (pin "4") (pinfunction "RT_4") (pintype "bidirectional"))
    )
    (net (code "75") (name "Net-(U5-SW)") (class "Default")
      (node (ref "C62") (pin "2") (pinfunction "2_2") (pintype "passive"))
      (node (ref "L6") (pin "1") (pinfunction "1_1") (pintype "bidirectional"))
      (node (ref "U5") (pin "2") (pinfunction "SW_2") (pintype "bidirectional"))
    )
    (net (code "76") (name "Net-(U5-TRSS)") (class "Default")
      (node (ref "C52") (pin "1") (pinfunction "1_1") (pintype "passive"))
      (node (ref "U5") (pin "7") (pinfunction "TRSS_7") (pintype "bidirectional"))
    )
    (net (code "77") (name "Net-(U11-CT)") (class "Default")
      (node (ref "R37") (pin "1") (pinfunction "1_1") (pintype "passive"))
      (node (ref "U11") (pin "6") (pinfunction "CT_6") (pintype "bidirectional"))
    )
    (net (code "78") (name "Net-(U11-INT)") (class "Default")
      (node (ref "R38") (pin "1") (pinfunction "1_1") (pintype "passive"))
      (node (ref "U11") (pin "5") (pinfunction "INT_5") (pintype "bidirectional"))
    )
    (net (code "79") (name "RPI_GND") (class "Default")
      (node (ref "J1") (pin "5") (pinfunction "5_5") (pintype "passive"))
      (node (ref "J2") (pin "5") (pinfunction "5_5") (pintype "passive"))
    )
    (net (code "80") (name "SCL1_I2C") (class "Default")
      (node (ref "J5") (pin "2") (pinfunction "2_2") (pintype "bidirectional"))
      (node (ref "X1") (pin "5") (pinfunction "P$5_5") (pintype "bidirectional"))
    )
    (net (code "81") (name "SDA1_I2C") (class "Default")
      (node (ref "J5") (pin "1") (pinfunction "1_1") (pintype "bidirectional"))
      (node (ref "X1") (pin "3") (pinfunction "P$3_3") (pintype "bidirectional"))
    )
    (net (code "82") (name "SPI0_CE0_N") (class "Default")
      (node (ref "J7") (pin "3") (pinfunction "3_3") (pintype "passive"))
      (node (ref "X1") (pin "24") (pinfunction "P$24_24") (pintype "bidirectional"))
    )
    (net (code "83") (name "SPI0_CE1_N") (class "Default")
      (node (ref "J7") (pin "5") (pinfunction "5_5") (pintype "passive"))
      (node (ref "X1") (pin "26") (pinfunction "P$26_26") (pintype "bidirectional"))
    )
    (net (code "84") (name "SPI0_CS") (class "Default")
      (node (ref "H1") (pin "1.10") (pinfunction "1.10_1.10") (pintype "bidirectional"))
      (node (ref "U11") (pin "4") (pinfunction "CS_4") (pintype "bidirectional"))
    )
    (net (code "85") (name "SPI0_MISO") (class "Default")
      (node (ref "J7") (pin "2") (pinfunction "2_2") (pintype "passive"))
      (node (ref "X1") (pin "21") (pinfunction "P$21_21") (pintype "bidirectional"))
    )
    (net (code "86") (name "SPI0_MOSI") (class "Default")
      (node (ref "J7") (pin "1") (pinfunction "1_1") (pintype "passive"))
      (node (ref "X1") (pin "19") (pinfunction "P$19_19") (pintype "bidirectional"))
    )
    (net (code "87") (name "SPI0_SCLK") (class "Default")
      (node (ref "J7") (pin "4") (pinfunction "4_4") (pintype "passive"))
      (node (ref "X1") (pin "23") (pinfunction "P$23_23") (pintype "bidirectional"))
    )
    (net (code "88") (name "SPI1_D0") (class "Default")
      (node (ref "H1") (pin "1.11") (pinfunction "1.11_1.11") (pintype "bidirectional"))
      (node (ref "U11") (pin "2") (pinfunction "DOUT_2") (pintype "bidirectional"))
    )
    (net (code "89") (name "SPI1_D1") (class "Default")
      (node (ref "H1") (pin "1.12") (pinfunction "1.12_1.12") (pintype "bidirectional"))
      (node (ref "U11") (pin "3") (pinfunction "DIN_3") (pintype "bidirectional"))
    )
    (net (code "90") (name "SPI1_SCLK") (class "Default")
      (node (ref "H1") (pin "1.9") (pinfunction "1.9_1.9") (pintype "bidirectional"))
      (node (ref "U11") (pin "1") (pinfunction "SCLK_1") (pintype "bidirectional"))
    )
    (net (code "91") (name "TORQUE_1A") (class "Default")
      (node (ref "J8") (pin "1") (pinfunction "1_1") (pintype "passive"))
      (node (ref "U1") (pin "2") (pinfunction "OUT1_2") (pintype "output"))
    )
    (net (code "92") (name "TORQUE_1B") (class "Default")
      (node (ref "J8") (pin "2") (pinfunction "2_2") (pintype "passive"))
      (node (ref "U1") (pin "4") (pinfunction "OUT2_4") (pintype "output"))
    )
    (net (code "93") (name "TORQUE_2A") (class "Default")
      (node (ref "J8") (pin "4") (pinfunction "4_4") (pintype "passive"))
      (node (ref "U1") (pin "7") (pinfunction "OUT3_7") (pintype "output"))
    )
    (net (code "94") (name "TORQUE_2B") (class "Default")
      (node (ref "J8") (pin "3") (pinfunction "3_3") (pintype "passive"))
      (node (ref "U1") (pin "5") (pinfunction "OUT4_5") (pintype "output"))
    )
    (net (code "95") (name "TORQUE_3A") (class "Default")
      (node (ref "J9") (pin "1") (pinfunction "1_1") (pintype "passive"))
      (node (ref "U2") (pin "2") (pinfunction "OUT1_2") (pintype "output"))
    )
    (net (code "96") (name "TORQUE_3B") (class "Default")
      (node (ref "J9") (pin "2") (pinfunction "2_2") (pintype "passive"))
      (node (ref "U2") (pin "4") (pinfunction "OUT2_4") (pintype "output"))
    )
    (net (code "97") (name "TORQUE_4A") (class "Default")
      (node (ref "J9") (pin "4") (pinfunction "4_4") (pintype "passive"))
      (node (ref "U2") (pin "7") (pinfunction "OUT3_7") (pintype "output"))
    )
    (net (code "98") (name "TORQUE_4B") (class "Default")
      (node (ref "J9") (pin "3") (pinfunction "3_3") (pintype "passive"))
      (node (ref "U2") (pin "5") (pinfunction "OUT4_5") (pintype "output"))
    )
    (net (code "99") (name "VCC") (class "Default")
      (node (ref "C13") (pin "1") (pinfunction "1_1") (pintype "passive"))
      (node (ref "C78") (pin "1") (pinfunction "1_1") (pintype "passive"))
      (node (ref "C79") (pin "1") (pinfunction "1_1") (pintype "passive"))
      (node (ref "C80") (pin "1") (pinfunction "1_1") (pintype "passive"))
      (node (ref "C81") (pin "1") (pinfunction "1_1") (pintype "passive"))
      (node (ref "D4") (pin "A") (pinfunction "A_A") (pintype "passive"))
      (node (ref "D4") (pin "C") (pinfunction "C_C") (pintype "passive"))
      (node (ref "R46") (pin "1") (pinfunction "1_1") (pintype "passive"))
      (node (ref "R8") (pin "2") (pinfunction "2_2") (pintype "passive"))
      (node (ref "R9") (pin "2") (pinfunction "2_2") (pintype "passive"))
      (node (ref "U$2") (pin "P$28") (pinfunction "ISN_P$28") (pintype "bidirectional"))
      (node (ref "U5") (pin "9") (pinfunction "VIN_9") (pintype "bidirectional"))
    )
    (net (code "100") (name "V_BATT") (class "Default")
      (node (ref "C1") (pin "1") (pinfunction "1_1") (pintype "passive"))
      (node (ref "C15") (pin "1") (pinfunction "1_1") (pintype "passive"))
      (node (ref "C16") (pin "1") (pinfunction "1_1") (pintype "passive"))
      (node (ref "C2") (pin "1") (pinfunction "1_1") (pintype "passive"))
      (node (ref "C4") (pin "1") (pinfunction "1_1") (pintype "passive"))
      (node (ref "H1") (pin "2.45") (pinfunction "2.45_2.45") (pintype "bidirectional"))
      (node (ref "H1") (pin "2.46") (pinfunction "2.46_2.46") (pintype "bidirectional"))
      (node (ref "M1") (pin "P$5") (pinfunction "D_P$5") (pintype "output"))
      (node (ref "M1") (pin "P$6") (pinfunction "D_P$6") (pintype "output"))
      (node (ref "M1") (pin "P$7") (pinfunction "D_P$7") (pintype "output"))
      (node (ref "M1") (pin "P$8") (pinfunction "D_P$8") (pintype "output"))
      (node (ref "M1") (pin "P$9") (pinfunction "D_P$9") (pintype "output"))
      (node (ref "R2") (pin "2") (pinfunction "2_2") (pintype "passive"))
      (node (ref "U$2") (pin "P$7") (pinfunction "VIN_P$7") (pintype "bidirectional"))
    )
    (net (code "101") (name "V_BATT_SENSE") (class "Default")
      (node (ref "R46") (pin "2") (pinfunction "2_2") (pintype "passive"))
      (node (ref "R47") (pin "2") (pinfunction "2_2") (pintype "passive"))
    )
    (net (code "102") (name "unconnected-(C13-Pad2)") (class "Default")
      (node (ref "C13") (pin "2") (pinfunction "2_2") (pintype "passive"))
    )
    (net (code "103") (name "unconnected-(H1-Pad1.1)") (class "Default")
      (node (ref "H1") (pin "1.1") (pinfunction "1.1_1.1") (pintype "bidirectional"))
    )
    (net (code "104") (name "unconnected-(H1-Pad1.2)") (class "Default")
      (node (ref "H1") (pin "1.2") (pinfunction "1.2_1.2") (pintype "bidirectional"))
    )
    (net (code "105") (name "unconnected-(H1-Pad1.3)") (class "Default")
      (node (ref "H1") (pin "1.3") (pinfunction "1.3_1.3") (pintype "bidirectional"))
    )
    (net (code "106") (name "unconnected-(H1-Pad1.4)") (class "Default")
      (node (ref "H1") (pin "1.4") (pinfunction "1.4_1.4") (pintype "bidirectional"))
    )
    (net (code "107") (name "unconnected-(H1-Pad1.5)") (class "Default")
      (node (ref "H1") (pin "1.5") (pinfunction "1.5_1.5") (pintype "bidirectional"))
    )
    (net (code "108") (name "unconnected-(H1-Pad1.6)") (class "Default")
      (node (ref "H1") (pin "1.6") (pinfunction "1.6_1.6") (pintype "bidirectional"))
    )
    (net (code "109") (name "unconnected-(H1-Pad1.7)") (class "Default")
      (node (ref "H1") (pin "1.7") (pinfunction "1.7_1.7") (pintype "bidirectional"))
    )
    (net (code "110") (name "unconnected-(H1-Pad1.8)") (class "Default")
      (node (ref "H1") (pin "1.8") (pinfunction "1.8_1.8") (pintype "bidirectional"))
    )
    (net (code "111") (name "unconnected-(H1-Pad1.13)") (class "Default")
      (node (ref "H1") (pin "1.13") (pinfunction "1.13_1.13") (pintype "bidirectional"))
    )
    (net (code "112") (name "unconnected-(H1-Pad1.14)") (class "Default")
      (node (ref "H1") (pin "1.14") (pinfunction "1.14_1.14") (pintype "bidirectional"))
    )
    (net (code "113") (name "unconnected-(H1-Pad1.15)") (class "Default")
      (node (ref "H1") (pin "1.15") (pinfunction "1.15_1.15") (pintype "bidirectional"))
    )
    (net (code "114") (name "unconnected-(H1-Pad1.16)") (class "Default")
      (node (ref "H1") (pin "1.16") (pinfunction "1.16_1.16") (pintype "bidirectional"))
    )
    (net (code "115") (name "unconnected-(H1-Pad1.21)") (class "Default")
      (node (ref "H1") (pin "1.21") (pinfunction "1.21_1.21") (pintype "bidirectional"))
    )
    (net (code "116") (name "unconnected-(H1-Pad1.22)") (class "Default")
      (node (ref "H1") (pin "1.22") (pinfunction "1.22_1.22") (pintype "bidirectional"))
    )
    (net (code "117") (name "unconnected-(H1-Pad1.31)") (class "Default")
      (node (ref "H1") (pin "1.31") (pinfunction "1.31_1.31") (pintype "bidirectional"))
    )
    (net (code "118") (name "unconnected-(H1-Pad1.32)") (class "Default")
      (node (ref "H1") (pin "1.32") (pinfunction "1.32_1.32") (pintype "bidirectional"))
    )
    (net (code "119") (name "unconnected-(H1-Pad1.33)") (class "Default")
      (node (ref "H1") (pin "1.33") (pinfunction "1.33_1.33") (pintype "bidirectional"))
    )
    (net (code "120") (name "unconnected-(H1-Pad1.34)") (class "Default")
      (node (ref "H1") (pin "1.34") (pinfunction "1.34_1.34") (pintype "bidirectional"))
    )
    (net (code "121") (name "unconnected-(H1-Pad1.35)") (class "Default")
      (node (ref "H1") (pin "1.35") (pinfunction "1.35_1.35") (pintype "bidirectional"))
    )
    (net (code "122") (name "unconnected-(H1-Pad1.36)") (class "Default")
      (node (ref "H1") (pin "1.36") (pinfunction "1.36_1.36") (pintype "bidirectional"))
    )
    (net (code "123") (name "unconnected-(H1-Pad1.37)") (class "Default")
      (node (ref "H1") (pin "1.37") (pinfunction "1.37_1.37") (pintype "bidirectional"))
    )
    (net (code "124") (name "unconnected-(H1-Pad1.39)") (class "Default")
      (node (ref "H1") (pin "1.39") (pinfunction "1.39_1.39") (pintype "bidirectional"))
    )
    (net (code "125") (name "unconnected-(H1-Pad1.41)") (class "Default")
      (node (ref "H1") (pin "1.41") (pinfunction "1.41_1.41") (pintype "bidirectional"))
    )
    (net (code "126") (name "unconnected-(H1-Pad1.43)") (class "Default")
      (node (ref "H1") (pin "1.43") (pinfunction "1.43_1.43") (pintype "bidirectional"))
    )
    (net (code "127") (name "unconnected-(H1-Pad1.45)") (class "Default")
      (node (ref "H1") (pin "1.45") (pinfunction "1.45_1.45") (pintype "bidirectional"))
    )
    (net (code "128") (name "unconnected-(H1-Pad1.47)") (class "Default")
      (node (ref "H1") (pin "1.47") (pinfunction "1.47_1.47") (pintype "bidirectional"))
    )
    (net (code "129") (name "unconnected-(H1-Pad1.49)") (class "Default")
      (node (ref "H1") (pin "1.49") (pinfunction "1.49_1.49") (pintype "bidirectional"))
    )
    (net (code "130") (name "unconnected-(H1-Pad1.50)") (class "Default")
      (node (ref "H1") (pin "1.50") (pinfunction "1.50_1.50") (pintype "bidirectional"))
    )
    (net (code "131") (name "unconnected-(H1-Pad1.51)") (class "Default")
      (node (ref "H1") (pin "1.51") (pinfunction "1.51_1.51") (pintype "bidirectional"))
    )
    (net (code "132") (name "unconnected-(H1-Pad1.52)") (class "Default")
      (node (ref "H1") (pin "1.52") (pinfunction "1.52_1.52") (pintype "bidirectional"))
    )
    (net (code "133") (name "unconnected-(H1-Pad2.1)") (class "Default")
      (node (ref "H1") (pin "2.1") (pinfunction "2.1_2.1") (pintype "bidirectional"))
    )
    (net (code "134") (name "unconnected-(H1-Pad2.2)") (class "Default")
      (node (ref "H1") (pin "2.2") (pinfunction "2.2_2.2") (pintype "bidirectional"))
    )
    (net (code "135") (name "unconnected-(H1-Pad2.3)") (class "Default")
      (node (ref "H1") (pin "2.3") (pinfunction "2.3_2.3") (pintype "bidirectional"))
    )
    (net (code "136") (name "unconnected-(H1-Pad2.4)") (class "Default")
      (node (ref "H1") (pin "2.4") (pinfunction "2.4_2.4") (pintype "bidirectional"))
    )
    (net (code "137") (name "unconnected-(H1-Pad2.5)") (class "Default")
      (node (ref "H1") (pin "2.5") (pinfunction "2.5_2.5") (pintype "bidirectional"))
    )
    (net (code "138") (name "unconnected-(H1-Pad2.6)") (class "Default")
      (node (ref "H1") (pin "2.6") (pinfunction "2.6_2.6") (pintype "bidirectional"))
    )
    (net (code "139") (name "unconnected-(H1-Pad2.9)") (class "Default")
      (node (ref "H1") (pin "2.9") (pinfunction "2.9_2.9") (pintype "bidirectional"))
    )
    (net (code "140") (name "unconnected-(H1-Pad2.10)") (class "Default")
      (node (ref "H1") (pin "2.10") (pinfunction "2.10_2.10") (pintype "bidirectional"))
    )
    (net (code "141") (name "unconnected-(H1-Pad2.11)") (class "Default")
      (node (ref "H1") (pin "2.11") (pinfunction "2.11_2.11") (pintype "bidirectional"))
    )
    (net (code "142") (name "unconnected-(H1-Pad2.12)") (class "Default")
      (node (ref "H1") (pin "2.12") (pinfunction "2.12_2.12") (pintype "bidirectional"))
    )
    (net (code "143") (name "unconnected-(H1-Pad2.18)") (class "Default")
      (node (ref "H1") (pin "2.18") (pinfunction "2.18_2.18") (pintype "bidirectional"))
    )
    (net (code "144") (name "unconnected-(H1-Pad2.23)") (class "Default")
      (node (ref "H1") (pin "2.23") (pinfunction "2.23_2.23") (pintype "bidirectional"))
    )
    (net (code "145") (name "unconnected-(H1-Pad2.24)") (class "Default")
      (node (ref "H1") (pin "2.24") (pinfunction "2.24_2.24") (pintype "bidirectional"))
    )
    (net (code "146") (name "unconnected-(H1-Pad2.31)") (class "Default")
      (node (ref "H1") (pin "2.31") (pinfunction "2.31_2.31") (pintype "bidirectional"))
    )
    (net (code "147") (name "unconnected-(H1-Pad2.33)") (class "Default")
      (node (ref "H1") (pin "2.33") (pinfunction "2.33_2.33") (pintype "bidirectional"))
    )
    (net (code "148") (name "unconnected-(H1-Pad2.34)") (class "Default")
      (node (ref "H1") (pin "2.34") (pinfunction "2.34_2.34") (pintype "bidirectional"))
    )
    (net (code "149") (name "unconnected-(H1-Pad2.35)") (class "Default")
      (node (ref "H1") (pin "2.35") (pinfunction "2.35_2.35") (pintype "bidirectional"))
    )
    (net (code "150") (name "unconnected-(H1-Pad2.36)") (class "Default")
      (node (ref "H1") (pin "2.36") (pinfunction "2.36_2.36") (pintype "bidirectional"))
    )
    (net (code "151") (name "unconnected-(H1-Pad2.37)") (class "Default")
      (node (ref "H1") (pin "2.37") (pinfunction "2.37_2.37") (pintype "bidirectional"))
    )
    (net (code "152") (name "unconnected-(H1-Pad2.38)") (class "Default")
      (node (ref "H1") (pin "2.38") (pinfunction "2.38_2.38") (pintype "bidirectional"))
    )
    (net (code "153") (name "unconnected-(H1-Pad2.39)") (class "Default")
      (node (ref "H1") (pin "2.39") (pinfunction "2.39_2.39") (pintype "bidirectional"))
    )
    (net (code "154") (name "unconnected-(H1-Pad2.40)") (class "Default")
      (node (ref "H1") (pin "2.40") (pinfunction "2.40_2.40") (pintype "bidirectional"))
    )
    (net (code "155") (name "unconnected-(H1-Pad2.41)") (class "Default")
      (node (ref "H1") (pin "2.41") (pinfunction "2.41_2.41") (pintype "bidirectional"))
    )
    (net (code "156") (name "unconnected-(H1-Pad2.42)") (class "Default")
      (node (ref "H1") (pin "2.42") (pinfunction "2.42_2.42") (pintype "bidirectional"))
    )
    (net (code "157") (name "unconnected-(H1-Pad2.43)") (class "Default")
      (node (ref "H1") (pin "2.43") (pinfunction "2.43_2.43") (pintype "bidirectional"))
    )
    (net (code "158") (name "unconnected-(H1-Pad2.44)") (class "Default")
      (node (ref "H1") (pin "2.44") (pinfunction "2.44_2.44") (pintype "bidirectional"))
    )
    (net (code "159") (name "unconnected-(H1-Pad2.49)") (class "Default")
      (node (ref "H1") (pin "2.49") (pinfunction "2.49_2.49") (pintype "bidirectional"))
    )
    (net (code "160") (name "unconnected-(H1-Pad2.50)") (class "Default")
      (node (ref "H1") (pin "2.50") (pinfunction "2.50_2.50") (pintype "bidirectional"))
    )
    (net (code "161") (name "unconnected-(H1-Pad2.51)") (class "Default")
      (node (ref "H1") (pin "2.51") (pinfunction "2.51_2.51") (pintype "bidirectional"))
    )
    (net (code "162") (name "unconnected-(H1-Pad2.52)") (class "Default")
      (node (ref "H1") (pin "2.52") (pinfunction "2.52_2.52") (pintype "bidirectional"))
    )
    (net (code "163") (name "unconnected-(H1-PadP$1)") (class "Default")
      (node (ref "H1") (pin "P$1") (pinfunction "P$1_P$1") (pintype "bidirectional"))
    )
    (net (code "164") (name "unconnected-(H1-PadP$2)") (class "Default")
      (node (ref "H1") (pin "P$2") (pinfunction "P$2_P$2") (pintype "bidirectional"))
    )
    (net (code "165") (name "unconnected-(H1-PadP$3)") (class "Default")
      (node (ref "H1") (pin "P$3") (pinfunction "P$3_P$3") (pintype "bidirectional"))
    )
    (net (code "166") (name "unconnected-(J8-MNT_1-Pad5)") (class "Default")
      (node (ref "J8") (pin "5") (pinfunction "MNT_1_5") (pintype "passive"))
    )
    (net (code "167") (name "unconnected-(J8-MNT_2-Pad6)") (class "Default")
      (node (ref "J8") (pin "6") (pinfunction "MNT_2_6") (pintype "passive"))
    )
    (net (code "168") (name "unconnected-(J9-MNT_1-Pad5)") (class "Default")
      (node (ref "J9") (pin "5") (pinfunction "MNT_1_5") (pintype "passive"))
    )
    (net (code "169") (name "unconnected-(J9-MNT_2-Pad6)") (class "Default")
      (node (ref "J9") (pin "6") (pinfunction "MNT_2_6") (pintype "passive"))
    )
    (net (code "170") (name "unconnected-(U$2-ISMON-PadP$27)") (class "Default")
      (node (ref "U$2") (pin "P$27") (pinfunction "ISMON_P$27") (pintype "bidirectional"))
    )
    (net (code "171") (name "unconnected-(U$2-LOADTG-PadP$20)") (class "Default")
      (node (ref "U$2") (pin "P$20") (pinfunction "LOADTG_P$20") (pintype "bidirectional"))
    )
    (net (code "172") (name "unconnected-(U1-MODE-Pad14)") (class "Default")
      (node (ref "U1") (pin "14") (pinfunction "MODE_14") (pintype "bidirectional"))
    )
    (net (code "173") (name "unconnected-(U2-MODE-Pad14)") (class "Default")
      (node (ref "U2") (pin "14") (pinfunction "MODE_14") (pintype "bidirectional"))
    )
    (net (code "174") (name "unconnected-(X1-P$2-Pad2)") (class "Default")
      (node (ref "X1") (pin "2") (pinfunction "P$2_2") (pintype "bidirectional"))
    )
    (net (code "175") (name "unconnected-(X1-P$4-Pad4)") (class "Default")
      (node (ref "X1") (pin "4") (pinfunction "P$4_4") (pintype "bidirectional"))
    )
    (net (code "176") (name "unconnected-(X1-P$6-Pad6)") (class "Default")
      (node (ref "X1") (pin "6") (pinfunction "P$6_6") (pintype "bidirectional"))
    )
    (net (code "177") (name "unconnected-(X1-P$7-Pad7)") (class "Default")
      (node (ref "X1") (pin "7") (pinfunction "P$7_7") (pintype "bidirectional"))
    )
    (net (code "178") (name "unconnected-(X1-P$8-Pad8)") (class "Default")
      (node (ref "X1") (pin "8") (pinfunction "P$8_8") (pintype "bidirectional"))
    )
    (net (code "179") (name "unconnected-(X1-P$9-Pad9)") (class "Default")
      (node (ref "X1") (pin "9") (pinfunction "P$9_9") (pintype "bidirectional"))
    )
    (net (code "180") (name "unconnected-(X1-P$10-Pad10)") (class "Default")
      (node (ref "X1") (pin "10") (pinfunction "P$10_10") (pintype "bidirectional"))
    )
    (net (code "181") (name "unconnected-(X1-P$12-Pad12)") (class "Default")
      (node (ref "X1") (pin "12") (pinfunction "P$12_12") (pintype "bidirectional"))
    )
    (net (code "182") (name "unconnected-(X1-P$14-Pad14)") (class "Default")
      (node (ref "X1") (pin "14") (pinfunction "P$14_14") (pintype "bidirectional"))
    )
    (net (code "183") (name "unconnected-(X1-P$17-Pad17)") (class "Default")
      (node (ref "X1") (pin "17") (pinfunction "P$17_17") (pintype "bidirectional"))
    )
    (net (code "184") (name "unconnected-(X1-P$20-Pad20)") (class "Default")
      (node (ref "X1") (pin "20") (pinfunction "P$20_20") (pintype "bidirectional"))
    )
    (net (code "185") (name "unconnected-(X1-P$25-Pad25)") (class "Default")
      (node (ref "X1") (pin "25") (pinfunction "P$25_25") (pintype "bidirectional"))
    )
    (net (code "186") (name "unconnected-(X1-P$27-Pad27)") (class "Default")
      (node (ref "X1") (pin "27") (pinfunction "P$27_27") (pintype "bidirectional"))
    )
    (net (code "187") (name "unconnected-(X1-P$28-Pad28)") (class "Default")
      (node (ref "X1") (pin "28") (pinfunction "P$28_28") (pintype "bidirectional"))
    )
    (net (code "188") (name "unconnected-(X1-P$29-Pad29)") (class "Default")
      (node (ref "X1") (pin "29") (pinfunction "P$29_29") (pintype "bidirectional"))
    )
    (net (code "189") (name "unconnected-(X1-P$30-Pad30)") (class "Default")
      (node (ref "X1") (pin "30") (pinfunction "P$30_30") (pintype "bidirectional"))
    )
    (net (code "190") (name "unconnected-(X1-P$34-Pad34)") (class "Default")
      (node (ref "X1") (pin "34") (pinfunction "P$34_34") (pintype "bidirectional"))
    )
    (net (code "191") (name "unconnected-(X1-P$39-Pad39)") (class "Default")
      (node (ref "X1") (pin "39") (pinfunction "P$39_39") (pintype "bidirectional"))
    )
    (net (code "192") (name "unconnected-(X2-Pad1)") (class "Default")
      (node (ref "X2") (pin "1") (pinfunction "1_1") (pintype "passive"))
    )
    (net (code "193") (name "unconnected-(X2AA-1-Pad33)") (class "Default")
      (node (ref "X2") (pin "33") (pinfunction "1_33") (pintype "passive"))
    )
    (net (code "194") (name "unconnected-(X2AB-1-Pad34)") (class "Default")
      (node (ref "X2") (pin "34") (pinfunction "1_34") (pintype "passive"))
    )
    (net (code "195") (name "unconnected-(X2AC-1-Pad35)") (class "Default")
      (node (ref "X2") (pin "35") (pinfunction "1_35") (pintype "passive"))
    )
    (net (code "196") (name "unconnected-(X2AD-1-Pad36)") (class "Default")
      (node (ref "X2") (pin "36") (pinfunction "1_36") (pintype "passive"))
    )
    (net (code "197") (name "unconnected-(X2AE-1-Pad37)") (class "Default")
      (node (ref "X2") (pin "37") (pinfunction "1_37") (pintype "passive"))
    )
    (net (code "198") (name "unconnected-(X2AF-1-Pad38)") (class "Default")
      (node (ref "X2") (pin "38") (pinfunction "1_38") (pintype "passive"))
    )
    (net (code "199") (name "unconnected-(X2AG-1-Pad39)") (class "Default")
      (node (ref "X2") (pin "39") (pinfunction "1_39") (pintype "passive"))
    )
    (net (code "200") (name "unconnected-(X2AH-1-Pad4)") (class "Default")
      (node (ref "X2") (pin "4") (pinfunction "1_4") (pintype "passive"))
    )
    (net (code "201") (name "unconnected-(X2AI-1-Pad40)") (class "Default")
      (node (ref "X2") (pin "40") (pinfunction "1_40") (pintype "passive"))
    )
    (net (code "202") (name "unconnected-(X2AJ-1-Pad5)") (class "Default")
      (node (ref "X2") (pin "5") (pinfunction "1_5") (pintype "passive"))
    )
    (net (code "203") (name "unconnected-(X2AK-1-Pad6)") (class "Default")
      (node (ref "X2") (pin "6") (pinfunction "1_6") (pintype "passive"))
    )
    (net (code "204") (name "unconnected-(X2AL-1-Pad7)") (class "Default")
      (node (ref "X2") (pin "7") (pinfunction "1_7") (pintype "passive"))
    )
    (net (code "205") (name "unconnected-(X2AM-1-Pad8)") (class "Default")
      (node (ref "X2") (pin "8") (pinfunction "1_8") (pintype "passive"))
    )
    (net (code "206") (name "unconnected-(X2AN-1-Pad9)") (class "Default")
      (node (ref "X2") (pin "9") (pinfunction "1_9") (pintype "passive"))
    )
    (net (code "207") (name "unconnected-(X2B-1-Pad10)") (class "Default")
      (node (ref "X2") (pin "10") (pinfunction "1_10") (pintype "passive"))
    )
    (net (code "208") (name "unconnected-(X2C-1-Pad11)") (class "Default")
      (node (ref "X2") (pin "11") (pinfunction "1_11") (pintype "passive"))
    )
    (net (code "209") (name "unconnected-(X2D-1-Pad12)") (class "Default")
      (node (ref "X2") (pin "12") (pinfunction "1_12") (pintype "passive"))
    )
    (net (code "210") (name "unconnected-(X2E-1-Pad13)") (class "Default")
      (node (ref "X2") (pin "13") (pinfunction "1_13") (pintype "passive"))
    )
    (net (code "211") (name "unconnected-(X2F-1-Pad14)") (class "Default")
      (node (ref "X2") (pin "14") (pinfunction "1_14") (pintype "passive"))
    )
    (net (code "212") (name "unconnected-(X2G-1-Pad15)") (class "Default")
      (node (ref "X2") (pin "15") (pinfunction "1_15") (pintype "passive"))
    )
    (net (code "213") (name "unconnected-(X2H-1-Pad16)") (class "Default")
      (node (ref "X2") (pin "16") (pinfunction "1_16") (pintype "passive"))
    )
    (net (code "214") (name "unconnected-(X2I-1-Pad17)") (class "Default")
      (node (ref "X2") (pin "17") (pinfunction "1_17") (pintype "passive"))
    )
    (net (code "215") (name "unconnected-(X2J-1-Pad18)") (class "Default")
      (node (ref "X2") (pin "18") (pinfunction "1_18") (pintype "passive"))
    )
    (net (code "216") (name "unconnected-(X2K-1-Pad19)") (class "Default")
      (node (ref "X2") (pin "19") (pinfunction "1_19") (pintype "passive"))
    )
    (net (code "217") (name "unconnected-(X2L-1-Pad2)") (class "Default")
      (node (ref "X2") (pin "2") (pinfunction "1_2") (pintype "passive"))
    )
    (net (code "218") (name "unconnected-(X2M-1-Pad20)") (class "Default")
      (node (ref "X2") (pin "20") (pinfunction "1_20") (pintype "passive"))
    )
    (net (code "219") (name "unconnected-(X2N-1-Pad21)") (class "Default")
      (node (ref "X2") (pin "21") (pinfunction "1_21") (pintype "passive"))
    )
    (net (code "220") (name "unconnected-(X2O-1-Pad22)") (class "Default")
      (node (ref "X2") (pin "22") (pinfunction "1_22") (pintype "passive"))
    )
    (net (code "221") (name "unconnected-(X2P-1-Pad23)") (class "Default")
      (node (ref "X2") (pin "23") (pinfunction "1_23") (pintype "passive"))
    )
    (net (code "222") (name "unconnected-(X2Q-1-Pad24)") (class "Default")
      (node (ref "X2") (pin "24") (pinfunction "1_24") (pintype "passive"))
    )
    (net (code "223") (name "unconnected-(X2R-1-Pad25)") (class "Default")
      (node (ref "X2") (pin "25") (pinfunction "1_25") (pintype "passive"))
    )
    (net (code "224") (name "unconnected-(X2S-1-Pad26)") (class "Default")
      (node (ref "X2") (pin "26") (pinfunction "1_26") (pintype "passive"))
    )
    (net (code "225") (name "unconnected-(X2T-1-Pad27)") (class "Default")
      (node (ref "X2") (pin "27") (pinfunction "1_27") (pintype "passive"))
    )
    (net (code "226") (name "unconnected-(X2U-1-Pad28)") (class "Default")
      (node (ref "X2") (pin "28") (pinfunction "1_28") (pintype "passive"))
    )
    (net (code "227") (name "unconnected-(X2V-1-Pad29)") (class "Default")
      (node (ref "X2") (pin "29") (pinfunction "1_29") (pintype "passive"))
    )
    (net (code "228") (name "unconnected-(X2W-1-Pad3)") (class "Default")
      (node (ref "X2") (pin "3") (pinfunction "1_3") (pintype "passive"))
    )
    (net (code "229") (name "unconnected-(X2X-1-Pad30)") (class "Default")
      (node (ref "X2") (pin "30") (pinfunction "1_30") (pintype "passive"))
    )
    (net (code "230") (name "unconnected-(X2Y-1-Pad31)") (class "Default")
      (node (ref "X2") (pin "31") (pinfunction "1_31") (pintype "passive"))
    )
    (net (code "231") (name "unconnected-(X2Z-1-Pad32)") (class "Default")
      (node (ref "X2") (pin "32") (pinfunction "1_32") (pintype "passive"))
    )
  )
)
